# routev3_5_poly.net
KiCad netlist of a schematic drawn in EAGLE
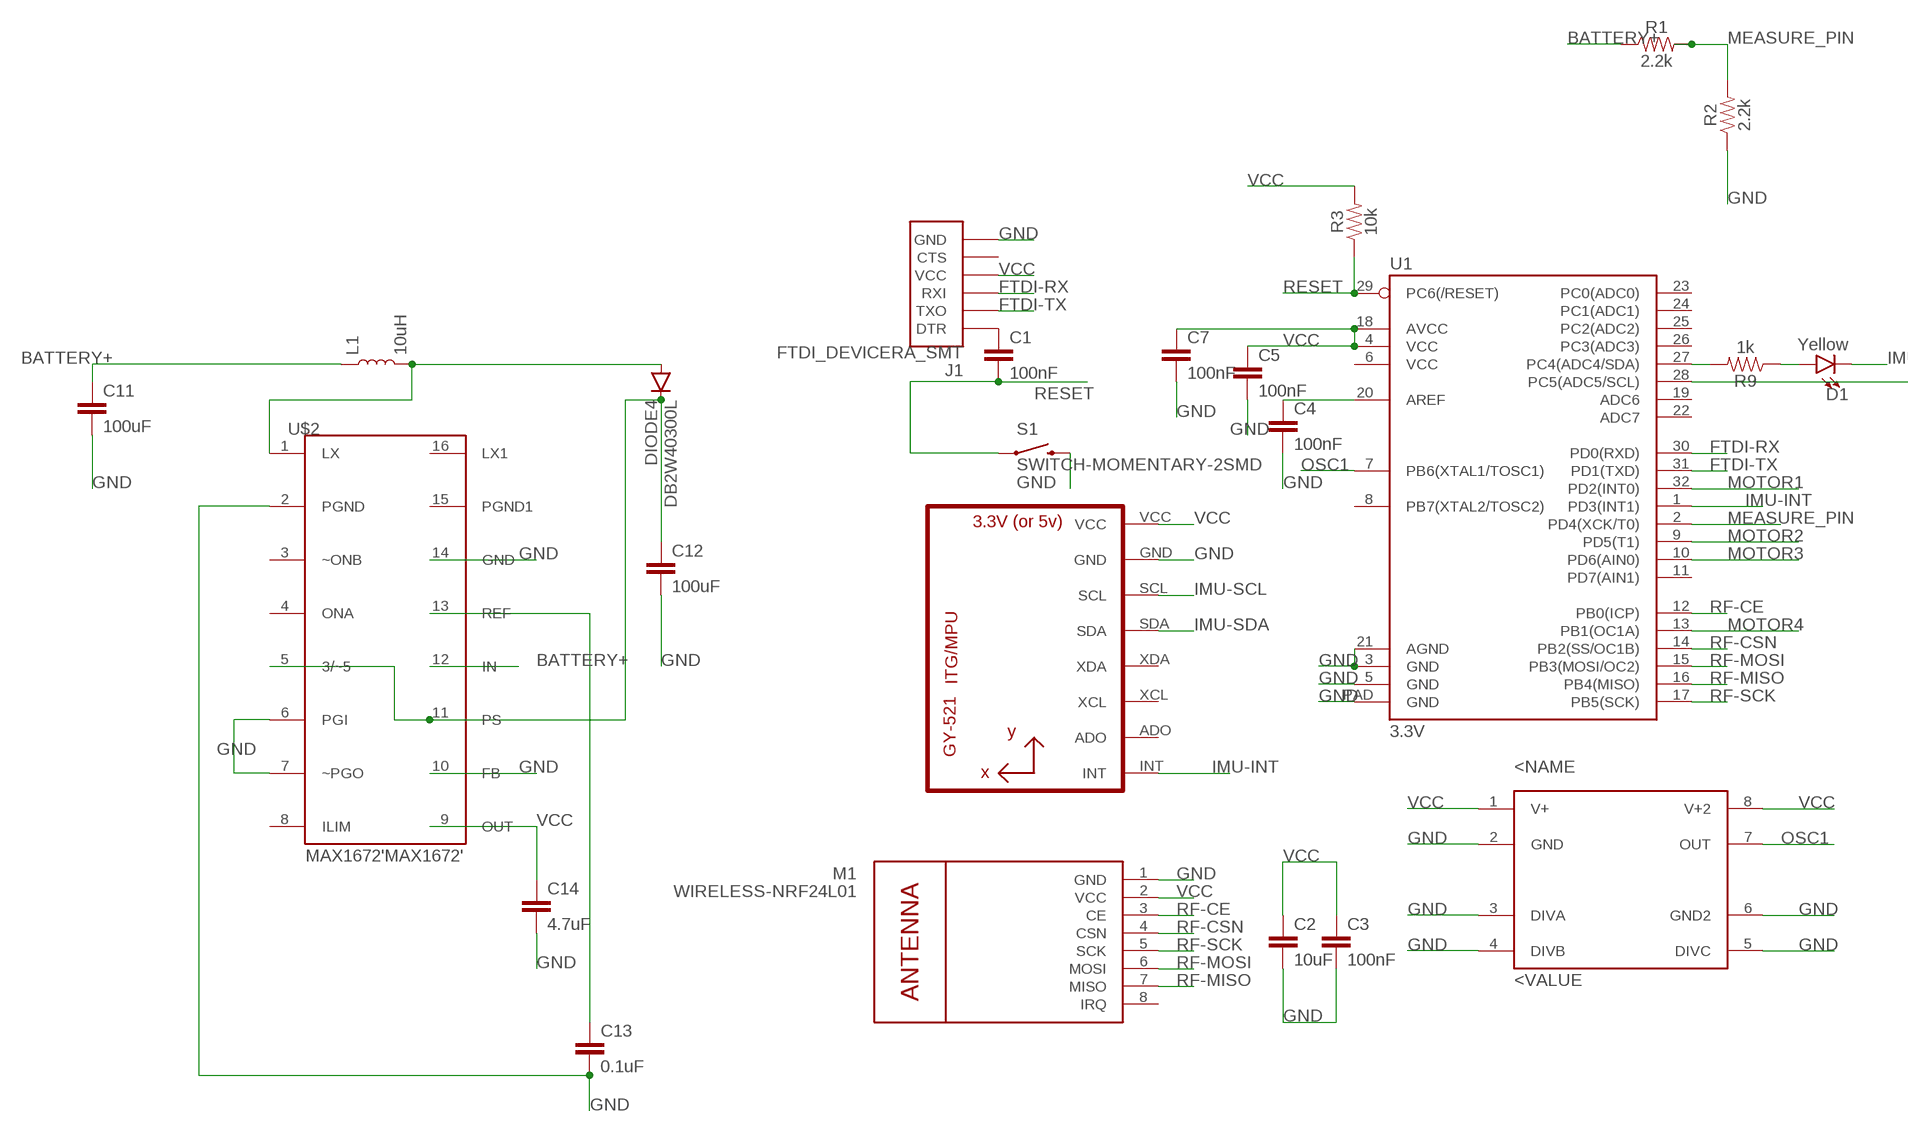
[diagram p0: schematic, sheet 1, part 1 of 2]
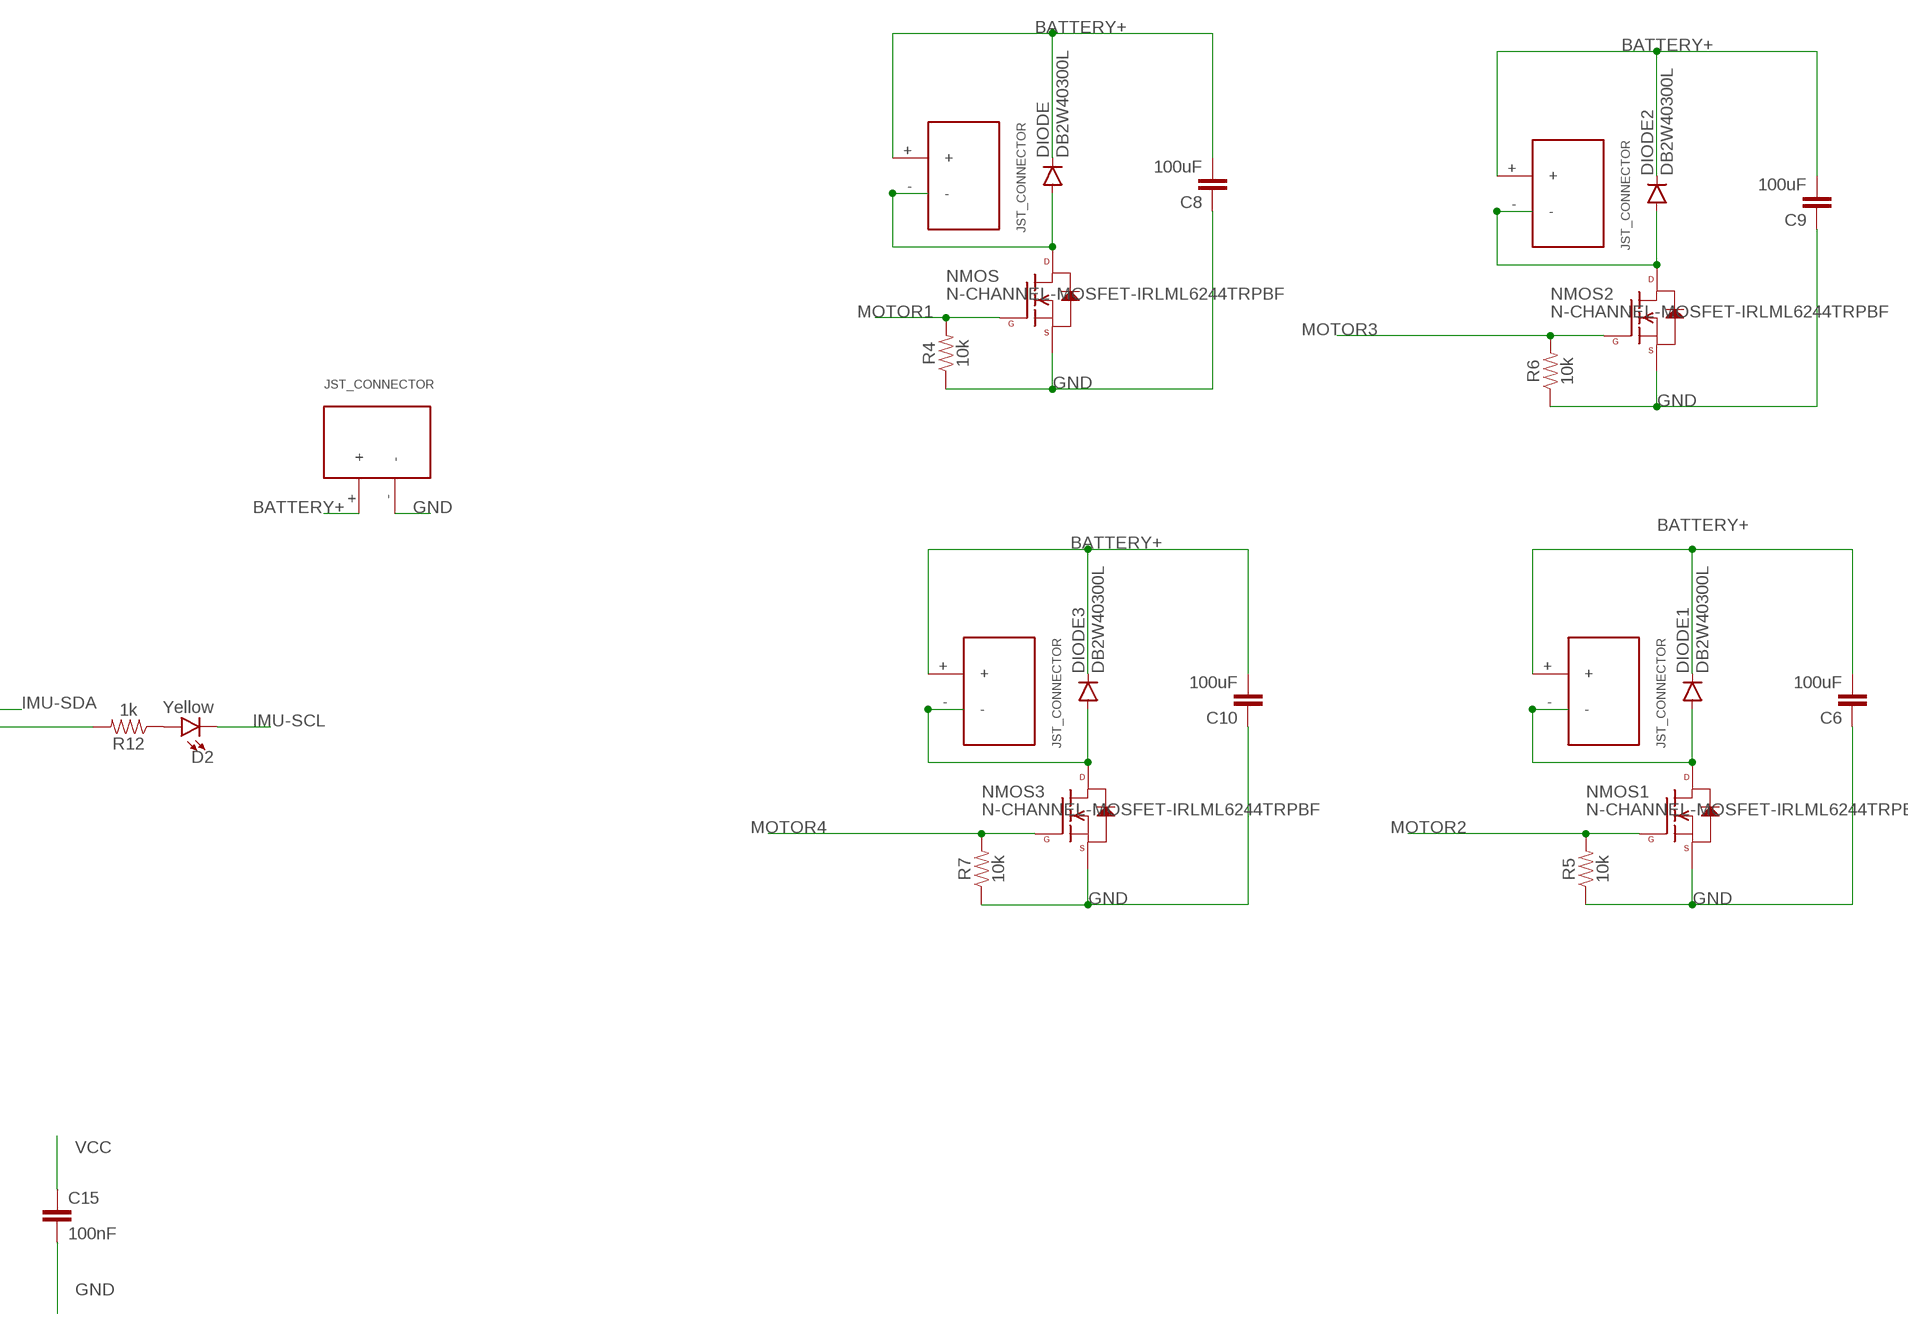
[diagram p1: schematic, sheet 1, part 2 of 2]

(export (version "E")
  (design (tool "Eeschema 10.0.6"))
  (components
    (comp (ref "C1")
      (value "100nF")
      (footprint "eagle-import:0603-CAP")
      (libsource (lib "eagle-import") (part "0.1UF-25V(+80/-20%)(0603)"))
    )
    (comp (ref "C2")
      (value "10uF")
      (footprint "eagle-import:0603-CAP")
      (libsource (lib "eagle-import") (part "CAP0603-CAP"))
    )
    (comp (ref "C3")
      (value "100nF")
      (footprint "eagle-import:0603-CAP")
      (libsource (lib "eagle-import") (part "CAP0603-CAP"))
    )
    (comp (ref "C4")
      (value "100nF")
      (footprint "eagle-import:0603-CAP")
      (libsource (lib "eagle-import") (part "CAP0603-CAP"))
    )
    (comp (ref "C5")
      (value "100nF")
      (footprint "eagle-import:0603-CAP")
      (libsource (lib "eagle-import") (part "CAP0603-CAP"))
    )
    (comp (ref "C6")
      (value "100uF")
      (footprint "eagle-import:0603-CAP")
      (libsource (lib "eagle-import") (part "CAP0603-CAP"))
    )
    (comp (ref "C7")
      (value "100nF")
      (footprint "eagle-import:0603-CAP")
      (libsource (lib "eagle-import") (part "CAP0603-CAP"))
    )
    (comp (ref "C8")
      (value "100uF")
      (footprint "eagle-import:0603-CAP")
      (libsource (lib "eagle-import") (part "CAP0603-CAP"))
    )
    (comp (ref "C9")
      (value "100uF")
      (footprint "eagle-import:0603-CAP")
      (libsource (lib "eagle-import") (part "CAP0603-CAP"))
    )
    (comp (ref "C10")
      (value "100uF")
      (footprint "eagle-import:0603-CAP")
      (libsource (lib "eagle-import") (part "CAP0603-CAP"))
    )
    (comp (ref "C11")
      (value "100uF")
      (footprint "eagle-import:0603-CAP")
      (libsource (lib "eagle-import") (part "CAP0603-CAP"))
    )
    (comp (ref "C12")
      (value "100uF")
      (footprint "eagle-import:0603-CAP")
      (libsource (lib "eagle-import") (part "CAP0603-CAP"))
    )
    (comp (ref "C13")
      (value "0.1uF")
      (footprint "eagle-import:0603-CAP")
      (libsource (lib "eagle-import") (part "CAP0603-CAP"))
    )
    (comp (ref "C14")
      (value "4.7uF")
      (footprint "eagle-import:0603-CAP")
      (libsource (lib "eagle-import") (part "CAP0603-CAP"))
    )
    (comp (ref "C15")
      (value "100nF")
      (footprint "eagle-import:0603-CAP")
      (libsource (lib "eagle-import") (part "0.1UF-25V(+80/-20%)(0603)"))
    )
    (comp (ref "D1")
      (value "Yellow")
      (footprint "eagle-import:LED-1206")
      (libsource (lib "eagle-import") (part "LED-YELLOWLILYPAD"))
    )
    (comp (ref "D2")
      (value "Yellow")
      (footprint "eagle-import:LED-1206")
      (libsource (lib "eagle-import") (part "LED-YELLOWLILYPAD"))
    )
    (comp (ref "DIODE")
      (value "DB2W40300L")
      (footprint "eagle-import:MINI2-F3-B")
      (libsource (lib "eagle-import") (part "DB2W40300L"))
    )
    (comp (ref "DIODE1")
      (value "DB2W40300L")
      (footprint "eagle-import:MINI2-F3-B")
      (libsource (lib "eagle-import") (part "DB2W40300L"))
    )
    (comp (ref "DIODE2")
      (value "DB2W40300L")
      (footprint "eagle-import:MINI2-F3-B")
      (libsource (lib "eagle-import") (part "DB2W40300L"))
    )
    (comp (ref "DIODE3")
      (value "DB2W40300L")
      (footprint "eagle-import:MINI2-F3-B")
      (libsource (lib "eagle-import") (part "DB2W40300L"))
    )
    (comp (ref "DIODE4")
      (value "DB2W40300L")
      (footprint "eagle-import:MINI2-F3-B")
      (libsource (lib "eagle-import") (part "DB2W40300L"))
    )
    (comp (ref "J1")
      (value "FTDI_DEVICERA_SMT")
      (footprint "eagle-import:FTDI_DEVICE_RA_SMT")
      (libsource (lib "eagle-import") (part "FTDI_DEVICERA_SMT"))
    )
    (comp (ref "L1")
      (value "10uH")
      (footprint "eagle-import:0603")
      (libsource (lib "eagle-import") (part "INDUCTOR-0603-33NH"))
    )
    (comp (ref "M1")
      (value "WIRELESS-NRF24L01")
      (footprint "eagle-import:WIRELESS-NRF24L01")
      (libsource (lib "eagle-import") (part "WIRELESS-NRF24L01"))
    )
    (comp (ref "MOTOR")
      (value "JST_CONNECTOR_FEMALE")
      (footprint "eagle-import:JST_CONNECTOR_FEMALE")
      (libsource (lib "eagle-import") (part "JST_CONNECTOR_FEMALE"))
    )
    (comp (ref "MOTOR1")
      (value "JST_CONNECTOR_FEMALE")
      (footprint "eagle-import:JST_CONNECTOR_FEMALE")
      (libsource (lib "eagle-import") (part "JST_CONNECTOR_FEMALE"))
    )
    (comp (ref "MOTOR2")
      (value "JST_CONNECTOR_FEMALE")
      (footprint "eagle-import:JST_CONNECTOR_FEMALE")
      (libsource (lib "eagle-import") (part "JST_CONNECTOR_FEMALE"))
    )
    (comp (ref "MOTOR3")
      (value "JST_CONNECTOR_FEMALE")
      (footprint "eagle-import:JST_CONNECTOR_FEMALE")
      (libsource (lib "eagle-import") (part "JST_CONNECTOR_FEMALE"))
    )
    (comp (ref "NMOS")
      (value "N-CHANNEL-MOSFET-IRLML6244TRPBF")
      (footprint "eagle-import:SOT23-3")
      (libsource (lib "eagle-import") (part "N-CHANNEL-MOSFET-IRLML6244TRPBF"))
    )
    (comp (ref "NMOS1")
      (value "N-CHANNEL-MOSFET-IRLML6244TRPBF")
      (footprint "eagle-import:SOT23-3")
      (libsource (lib "eagle-import") (part "N-CHANNEL-MOSFET-IRLML6244TRPBF"))
    )
    (comp (ref "NMOS2")
      (value "N-CHANNEL-MOSFET-IRLML6244TRPBF")
      (footprint "eagle-import:SOT23-3")
      (libsource (lib "eagle-import") (part "N-CHANNEL-MOSFET-IRLML6244TRPBF"))
    )
    (comp (ref "NMOS3")
      (value "N-CHANNEL-MOSFET-IRLML6244TRPBF")
      (footprint "eagle-import:SOT23-3")
      (libsource (lib "eagle-import") (part "N-CHANNEL-MOSFET-IRLML6244TRPBF"))
    )
    (comp (ref "R1")
      (value "2.2k")
      (footprint "eagle-import:0603")
      (libsource (lib "eagle-import") (part "2.2KOHM-0603-1/10W-1%"))
    )
    (comp (ref "R2")
      (value "2.2k")
      (footprint "eagle-import:0603")
      (libsource (lib "eagle-import") (part "2.2KOHM-0603-1/10W-1%"))
    )
    (comp (ref "R3")
      (value "10k")
      (footprint "eagle-import:0603")
      (libsource (lib "eagle-import") (part "2.2KOHM-0603-1/10W-1%"))
    )
    (comp (ref "R4")
      (value "10k")
      (footprint "eagle-import:0603")
      (libsource (lib "eagle-import") (part "2.2KOHM-0603-1/10W-1%"))
    )
    (comp (ref "R5")
      (value "10k")
      (footprint "eagle-import:0603")
      (libsource (lib "eagle-import") (part "2.2KOHM-0603-1/10W-1%"))
    )
    (comp (ref "R6")
      (value "10k")
      (footprint "eagle-import:0603")
      (libsource (lib "eagle-import") (part "2.2KOHM-0603-1/10W-1%"))
    )
    (comp (ref "R7")
      (value "10k")
      (footprint "eagle-import:0603")
      (libsource (lib "eagle-import") (part "2.2KOHM-0603-1/10W-1%"))
    )
    (comp (ref "R9")
      (value "1k")
      (footprint "eagle-import:0603")
      (libsource (lib "eagle-import") (part "2.2KOHM-0603-1/10W-1%"))
    )
    (comp (ref "R12")
      (value "1k")
      (footprint "eagle-import:0603")
      (libsource (lib "eagle-import") (part "2.2KOHM-0603-1/10W-1%"))
    )
    (comp (ref "S1")
      (value "SWITCH-MOMENTARY-2SMD")
      (footprint "eagle-import:TACTILE-SWITCH-SMD")
      (libsource (lib "eagle-import") (part "SWITCH-MOMENTARY-2SMD"))
    )
    (comp (ref "U$1")
      (value "JST_CONNECTOR_FEMALE")
      (footprint "eagle-import:JST_CONNECTOR_FEMALE")
      (libsource (lib "eagle-import") (part "JST_CONNECTOR_FEMALE"))
    )
    (comp (ref "U$2")
      (value "MAX1672'MAX1672'")
      (footprint "eagle-import:21-0055H_16")
      (libsource (lib "eagle-import") (part "MAX1672'MAX1672'"))
    )
    (comp (ref "U$3")
      (value "LTC6930CMS8-8.19LTC6930CMS8-8.19")
      (footprint "eagle-import:SOP65P490X110-8N")
      (libsource (lib "eagle-import") (part "LTC6930CMS8-8.19LTC6930CMS8-8.19"))
    )
    (comp (ref "U1")
      (value "3.3V")
      (footprint "eagle-import:MLF32-PAD")
      (libsource (lib "eagle-import") (part "ATMEGA328P_MLFMLF32"))
    )
    (comp (ref "U2")
      (value "GY-521MPU6050")
      (footprint "eagle-import:GY-521")
      (libsource (lib "eagle-import") (part "GY-521MPU6050"))
    )
  )
  (nets
    (net (code "1") (name "BATTERY+") (class "Default")
      (node (ref "C10") (pin "2") (pinfunction "2_2") (pintype "passive"))
      (node (ref "C11") (pin "1") (pinfunction "1_1") (pintype "passive"))
      (node (ref "C6") (pin "2") (pinfunction "2_2") (pintype "passive"))
      (node (ref "C8") (pin "2") (pinfunction "2_2") (pintype "passive"))
      (node (ref "C9") (pin "2") (pinfunction "2_2") (pintype "passive"))
      (node (ref "DIODE") (pin "NEG") (pinfunction "GPIN_NEG") (pintype "passive"))
      (node (ref "DIODE1") (pin "NEG") (pinfunction "GPIN_NEG") (pintype "passive"))
      (node (ref "DIODE2") (pin "NEG") (pinfunction "GPIN_NEG") (pintype "passive"))
      (node (ref "DIODE3") (pin "NEG") (pinfunction "GPIN_NEG") (pintype "passive"))
      (node (ref "L1") (pin "1") (pinfunction "1_1") (pintype "passive"))
      (node (ref "MOTOR") (pin "+") (pinfunction "+_+") (pintype "bidirectional"))
      (node (ref "MOTOR1") (pin "+") (pinfunction "+_+") (pintype "bidirectional"))
      (node (ref "MOTOR2") (pin "+") (pinfunction "+_+") (pintype "bidirectional"))
      (node (ref "MOTOR3") (pin "+") (pinfunction "+_+") (pintype "bidirectional"))
      (node (ref "R1") (pin "1") (pinfunction "1_1") (pintype "passive"))
      (node (ref "U$1") (pin "+") (pinfunction "+_+") (pintype "bidirectional"))
      (node (ref "U$2") (pin "12") (pinfunction "IN_12") (pintype "bidirectional"))
    )
    (net (code "2") (name "FTDI-RX") (class "Default")
      (node (ref "J1") (pin "3") (pinfunction "RXI_3") (pintype "bidirectional"))
      (node (ref "U1") (pin "30") (pinfunction "PD0(RXD)_30") (pintype "bidirectional"))
    )
    (net (code "3") (name "FTDI-TX") (class "Default")
      (node (ref "J1") (pin "2") (pinfunction "TXO_2") (pintype "bidirectional"))
      (node (ref "U1") (pin "31") (pinfunction "PD1(TXD)_31") (pintype "bidirectional"))
    )
    (net (code "4") (name "GND") (class "Default")
      (node (ref "C10") (pin "1") (pinfunction "1_1") (pintype "passive"))
      (node (ref "C11") (pin "2") (pinfunction "2_2") (pintype "passive"))
      (node (ref "C12") (pin "2") (pinfunction "2_2") (pintype "passive"))
      (node (ref "C13") (pin "2") (pinfunction "2_2") (pintype "passive"))
      (node (ref "C14") (pin "2") (pinfunction "2_2") (pintype "passive"))
      (node (ref "C15") (pin "2") (pinfunction "2_2") (pintype "passive"))
      (node (ref "C2") (pin "2") (pinfunction "2_2") (pintype "passive"))
      (node (ref "C3") (pin "2") (pinfunction "2_2") (pintype "passive"))
      (node (ref "C4") (pin "2") (pinfunction "2_2") (pintype "passive"))
      (node (ref "C5") (pin "2") (pinfunction "2_2") (pintype "passive"))
      (node (ref "C6") (pin "1") (pinfunction "1_1") (pintype "passive"))
      (node (ref "C7") (pin "2") (pinfunction "2_2") (pintype "passive"))
      (node (ref "C8") (pin "1") (pinfunction "1_1") (pintype "passive"))
      (node (ref "C9") (pin "1") (pinfunction "1_1") (pintype "passive"))
      (node (ref "J1") (pin "6") (pinfunction "GND_6") (pintype "bidirectional"))
      (node (ref "M1") (pin "1") (pinfunction "GND_1") (pintype "power_in"))
      (node (ref "NMOS") (pin "2") (pinfunction "S_2") (pintype "passive"))
      (node (ref "NMOS1") (pin "2") (pinfunction "S_2") (pintype "passive"))
      (node (ref "NMOS2") (pin "2") (pinfunction "S_2") (pintype "passive"))
      (node (ref "NMOS3") (pin "2") (pinfunction "S_2") (pintype "passive"))
      (node (ref "R2") (pin "1") (pinfunction "1_1") (pintype "passive"))
      (node (ref "R4") (pin "1") (pinfunction "1_1") (pintype "passive"))
      (node (ref "R5") (pin "1") (pinfunction "1_1") (pintype "passive"))
      (node (ref "R6") (pin "1") (pinfunction "1_1") (pintype "passive"))
      (node (ref "R7") (pin "1") (pinfunction "1_1") (pintype "passive"))
      (node (ref "S1") (pin "3") (pinfunction "2_3") (pintype "passive"))
      (node (ref "U$1") (pin "-") (pinfunction "-_-") (pintype "bidirectional"))
      (node (ref "U$2") (pin "10") (pinfunction "FB_10") (pintype "bidirectional"))
      (node (ref "U$2") (pin "14") (pinfunction "GND_14") (pintype "bidirectional"))
      (node (ref "U$2") (pin "2") (pinfunction "PGND_2") (pintype "bidirectional"))
      (node (ref "U$2") (pin "6") (pinfunction "PGI_6") (pintype "bidirectional"))
      (node (ref "U$2") (pin "7") (pinfunction "~{PGO}_7") (pintype "bidirectional"))
      (node (ref "U$3") (pin "2") (pinfunction "GND_2") (pintype "bidirectional"))
      (node (ref "U$3") (pin "3") (pinfunction "DIVA_3") (pintype "bidirectional"))
      (node (ref "U$3") (pin "4") (pinfunction "DIVB_4") (pintype "bidirectional"))
      (node (ref "U$3") (pin "5") (pinfunction "DIVC_5") (pintype "bidirectional"))
      (node (ref "U$3") (pin "6") (pinfunction "GND2_6") (pintype "bidirectional"))
      (node (ref "U1") (pin "21") (pinfunction "AGND_21") (pintype "bidirectional"))
      (node (ref "U1") (pin "3") (pinfunction "GND_3") (pintype "bidirectional"))
      (node (ref "U1") (pin "5") (pinfunction "GND_5") (pintype "bidirectional"))
      (node (ref "U1") (pin "PAD") (pinfunction "GND_PAD") (pintype "bidirectional"))
      (node (ref "U2") (pin "GND") (pinfunction "GND_GND") (pintype "bidirectional"))
    )
    (net (code "5") (name "IMU-INT") (class "Default")
      (node (ref "U1") (pin "1") (pinfunction "PD3(INT1)_1") (pintype "bidirectional"))
      (node (ref "U2") (pin "INT") (pinfunction "INT_INT") (pintype "bidirectional"))
    )
    (net (code "6") (name "IMU-SCL") (class "Default")
      (node (ref "D2") (pin "C") (pinfunction "C_C") (pintype "passive"))
      (node (ref "U2") (pin "SCL") (pinfunction "SCL_SCL") (pintype "bidirectional"))
    )
    (net (code "7") (name "IMU-SDA") (class "Default")
      (node (ref "D1") (pin "C") (pinfunction "C_C") (pintype "passive"))
      (node (ref "U2") (pin "SDA") (pinfunction "SDA_SDA") (pintype "bidirectional"))
    )
    (net (code "8") (name "MEASURE_PIN") (class "Default")
      (node (ref "R1") (pin "2") (pinfunction "2_2") (pintype "passive"))
      (node (ref "R2") (pin "2") (pinfunction "2_2") (pintype "passive"))
      (node (ref "U1") (pin "2") (pinfunction "PD4(XCK/T0)_2") (pintype "bidirectional"))
    )
    (net (code "9") (name "MOTOR1") (class "Default")
      (node (ref "NMOS") (pin "1") (pinfunction "G_1") (pintype "passive"))
      (node (ref "R4") (pin "2") (pinfunction "2_2") (pintype "passive"))
      (node (ref "U1") (pin "32") (pinfunction "PD2(INT0)_32") (pintype "bidirectional"))
    )
    (net (code "10") (name "MOTOR2") (class "Default")
      (node (ref "NMOS1") (pin "1") (pinfunction "G_1") (pintype "passive"))
      (node (ref "R5") (pin "2") (pinfunction "2_2") (pintype "passive"))
      (node (ref "U1") (pin "9") (pinfunction "PD5(T1)_9") (pintype "bidirectional"))
    )
    (net (code "11") (name "MOTOR3") (class "Default")
      (node (ref "NMOS2") (pin "1") (pinfunction "G_1") (pintype "passive"))
      (node (ref "R6") (pin "2") (pinfunction "2_2") (pintype "passive"))
      (node (ref "U1") (pin "10") (pinfunction "PD6(AIN0)_10") (pintype "bidirectional"))
    )
    (net (code "12") (name "MOTOR4") (class "Default")
      (node (ref "NMOS3") (pin "1") (pinfunction "G_1") (pintype "passive"))
      (node (ref "R7") (pin "2") (pinfunction "2_2") (pintype "passive"))
      (node (ref "U1") (pin "13") (pinfunction "PB1(OC1A)_13") (pintype "bidirectional"))
    )
    (net (code "13") (name "Net-(D1-PadA)") (class "Default")
      (node (ref "D1") (pin "A") (pinfunction "A_A") (pintype "passive"))
      (node (ref "R9") (pin "1") (pinfunction "1_1") (pintype "passive"))
    )
    (net (code "14") (name "Net-(D2-PadA)") (class "Default")
      (node (ref "D2") (pin "A") (pinfunction "A_A") (pintype "passive"))
      (node (ref "R12") (pin "1") (pinfunction "1_1") (pintype "passive"))
    )
    (net (code "15") (name "Net-(DIODE-PPIN)") (class "Default")
      (node (ref "DIODE") (pin "POS") (pinfunction "PPIN_POS") (pintype "passive"))
      (node (ref "MOTOR") (pin "-") (pinfunction "-_-") (pintype "bidirectional"))
      (node (ref "NMOS") (pin "3") (pinfunction "D_3") (pintype "passive"))
    )
    (net (code "16") (name "Net-(DIODE1-PPIN)") (class "Default")
      (node (ref "DIODE1") (pin "POS") (pinfunction "PPIN_POS") (pintype "passive"))
      (node (ref "MOTOR1") (pin "-") (pinfunction "-_-") (pintype "bidirectional"))
      (node (ref "NMOS1") (pin "3") (pinfunction "D_3") (pintype "passive"))
    )
    (net (code "17") (name "Net-(DIODE2-PPIN)") (class "Default")
      (node (ref "DIODE2") (pin "POS") (pinfunction "PPIN_POS") (pintype "passive"))
      (node (ref "MOTOR2") (pin "-") (pinfunction "-_-") (pintype "bidirectional"))
      (node (ref "NMOS2") (pin "3") (pinfunction "D_3") (pintype "passive"))
    )
    (net (code "18") (name "Net-(DIODE3-PPIN)") (class "Default")
      (node (ref "DIODE3") (pin "POS") (pinfunction "PPIN_POS") (pintype "passive"))
      (node (ref "MOTOR3") (pin "-") (pinfunction "-_-") (pintype "bidirectional"))
      (node (ref "NMOS3") (pin "3") (pinfunction "D_3") (pintype "passive"))
    )
    (net (code "19") (name "Net-(DIODE4-GPIN)") (class "Default")
      (node (ref "C12") (pin "1") (pinfunction "1_1") (pintype "passive"))
      (node (ref "DIODE4") (pin "NEG") (pinfunction "GPIN_NEG") (pintype "passive"))
      (node (ref "U$2") (pin "11") (pinfunction "PS_11") (pintype "bidirectional"))
      (node (ref "U$2") (pin "5") (pinfunction "3/~{5}_5") (pintype "bidirectional"))
    )
    (net (code "20") (name "Net-(DIODE4-PPIN)") (class "Default")
      (node (ref "DIODE4") (pin "POS") (pinfunction "PPIN_POS") (pintype "passive"))
      (node (ref "L1") (pin "2") (pinfunction "2_2") (pintype "passive"))
      (node (ref "U$2") (pin "1") (pinfunction "LX_1") (pintype "bidirectional"))
    )
    (net (code "21") (name "Net-(J1-DTR)") (class "Default")
      (node (ref "C1") (pin "1") (pinfunction "1_1") (pintype "passive"))
      (node (ref "J1") (pin "1") (pinfunction "DTR_1") (pintype "bidirectional"))
    )
    (net (code "22") (name "Net-(U$2-REF)") (class "Default")
      (node (ref "C13") (pin "1") (pinfunction "1_1") (pintype "passive"))
      (node (ref "U$2") (pin "13") (pinfunction "REF_13") (pintype "bidirectional"))
    )
    (net (code "23") (name "Net-(U1-AREF)") (class "Default")
      (node (ref "C4") (pin "1") (pinfunction "1_1") (pintype "passive"))
      (node (ref "U1") (pin "20") (pinfunction "AREF_20") (pintype "bidirectional"))
    )
    (net (code "24") (name "Net-(U1-PC4(ADC4{slash}SDA))") (class "Default")
      (node (ref "R9") (pin "2") (pinfunction "2_2") (pintype "passive"))
      (node (ref "U1") (pin "27") (pinfunction "PC4(ADC4/SDA)_27") (pintype "bidirectional"))
    )
    (net (code "25") (name "Net-(U1-PC5(ADC5{slash}SCL))") (class "Default")
      (node (ref "R12") (pin "2") (pinfunction "2_2") (pintype "passive"))
      (node (ref "U1") (pin "28") (pinfunction "PC5(ADC5/SCL)_28") (pintype "bidirectional"))
    )
    (net (code "26") (name "OSC1") (class "Default")
      (node (ref "U$3") (pin "7") (pinfunction "OUT_7") (pintype "bidirectional"))
      (node (ref "U1") (pin "7") (pinfunction "PB6(XTAL1/TOSC1)_7") (pintype "bidirectional"))
    )
    (net (code "27") (name "RESET") (class "Default")
      (node (ref "C1") (pin "2") (pinfunction "2_2") (pintype "passive"))
      (node (ref "R3") (pin "1") (pinfunction "1_1") (pintype "passive"))
      (node (ref "S1") (pin "1") (pinfunction "1_1") (pintype "passive"))
      (node (ref "U1") (pin "29") (pinfunction "PC6(/RESET)_29") (pintype "bidirectional"))
    )
    (net (code "28") (name "RF-CE") (class "Default")
      (node (ref "M1") (pin "3") (pinfunction "CE_3") (pintype "bidirectional"))
      (node (ref "U1") (pin "12") (pinfunction "PB0(ICP)_12") (pintype "bidirectional"))
    )
    (net (code "29") (name "RF-CSN") (class "Default")
      (node (ref "M1") (pin "4") (pinfunction "CSN_4") (pintype "bidirectional"))
      (node (ref "U1") (pin "14") (pinfunction "PB2(SS/OC1B)_14") (pintype "bidirectional"))
    )
    (net (code "30") (name "RF-MISO") (class "Default")
      (node (ref "M1") (pin "7") (pinfunction "MISO_7") (pintype "bidirectional"))
      (node (ref "U1") (pin "16") (pinfunction "PB4(MISO)_16") (pintype "bidirectional"))
    )
    (net (code "31") (name "RF-MOSI") (class "Default")
      (node (ref "M1") (pin "6") (pinfunction "MOSI_6") (pintype "bidirectional"))
      (node (ref "U1") (pin "15") (pinfunction "PB3(MOSI/OC2)_15") (pintype "bidirectional"))
    )
    (net (code "32") (name "RF-SCK") (class "Default")
      (node (ref "M1") (pin "5") (pinfunction "SCK_5") (pintype "bidirectional"))
      (node (ref "U1") (pin "17") (pinfunction "PB5(SCK)_17") (pintype "bidirectional"))
    )
    (net (code "33") (name "VCC") (class "Default")
      (node (ref "C14") (pin "1") (pinfunction "1_1") (pintype "passive"))
      (node (ref "C15") (pin "1") (pinfunction "1_1") (pintype "passive"))
      (node (ref "C2") (pin "1") (pinfunction "1_1") (pintype "passive"))
      (node (ref "C3") (pin "1") (pinfunction "1_1") (pintype "passive"))
      (node (ref "C5") (pin "1") (pinfunction "1_1") (pintype "passive"))
      (node (ref "C7") (pin "1") (pinfunction "1_1") (pintype "passive"))
      (node (ref "J1") (pin "4") (pinfunction "VCC_4") (pintype "bidirectional"))
      (node (ref "M1") (pin "2") (pinfunction "VCC_2") (pintype "power_in"))
      (node (ref "R3") (pin "2") (pinfunction "2_2") (pintype "passive"))
      (node (ref "U$2") (pin "9") (pinfunction "OUT_9") (pintype "bidirectional"))
      (node (ref "U$3") (pin "1") (pinfunction "V+_1") (pintype "bidirectional"))
      (node (ref "U$3") (pin "8") (pinfunction "V+2_8") (pintype "bidirectional"))
      (node (ref "U1") (pin "18") (pinfunction "AVCC_18") (pintype "bidirectional"))
      (node (ref "U1") (pin "4") (pinfunction "VCC_4") (pintype "bidirectional"))
      (node (ref "U2") (pin "VCC") (pinfunction "VCC_VCC") (pintype "bidirectional"))
    )
    (net (code "34") (name "unconnected-(J1-CTS-Pad5)") (class "Default")
      (node (ref "J1") (pin "5") (pinfunction "CTS_5") (pintype "bidirectional"))
    )
    (net (code "35") (name "unconnected-(M1-IRQ-Pad8)") (class "Default")
      (node (ref "M1") (pin "8") (pinfunction "IRQ_8") (pintype "bidirectional"))
    )
    (net (code "36") (name "unconnected-(U$2-ILIM-Pad8)") (class "Default")
      (node (ref "U$2") (pin "8") (pinfunction "ILIM_8") (pintype "bidirectional"))
    )
    (net (code "37") (name "unconnected-(U$2-LX1-Pad16)") (class "Default")
      (node (ref "U$2") (pin "16") (pinfunction "LX1_16") (pintype "bidirectional"))
    )
    (net (code "38") (name "unconnected-(U$2-ONA-Pad4)") (class "Default")
      (node (ref "U$2") (pin "4") (pinfunction "ONA_4") (pintype "bidirectional"))
    )
    (net (code "39") (name "unconnected-(U$2-PGND1-Pad15)") (class "Default")
      (node (ref "U$2") (pin "15") (pinfunction "PGND1_15") (pintype "bidirectional"))
    )
    (net (code "40") (name "unconnected-(U$2-~{ONB}-Pad3)") (class "Default")
      (node (ref "U$2") (pin "3") (pinfunction "~{ONB}_3") (pintype "bidirectional"))
    )
    (net (code "41") (name "unconnected-(U1-ADC6-Pad19)") (class "Default")
      (node (ref "U1") (pin "19") (pinfunction "ADC6_19") (pintype "bidirectional"))
    )
    (net (code "42") (name "unconnected-(U1-ADC7-Pad22)") (class "Default")
      (node (ref "U1") (pin "22") (pinfunction "ADC7_22") (pintype "bidirectional"))
    )
    (net (code "43") (name "unconnected-(U1-PB7(XTAL2{slash}TOSC2)-Pad8)") (class "Default")
      (node (ref "U1") (pin "8") (pinfunction "PB7(XTAL2/TOSC2)_8") (pintype "bidirectional"))
    )
    (net (code "44") (name "unconnected-(U1-PC0(ADC0)-Pad23)") (class "Default")
      (node (ref "U1") (pin "23") (pinfunction "PC0(ADC0)_23") (pintype "bidirectional"))
    )
    (net (code "45") (name "unconnected-(U1-PC1(ADC1)-Pad24)") (class "Default")
      (node (ref "U1") (pin "24") (pinfunction "PC1(ADC1)_24") (pintype "bidirectional"))
    )
    (net (code "46") (name "unconnected-(U1-PC2(ADC2)-Pad25)") (class "Default")
      (node (ref "U1") (pin "25") (pinfunction "PC2(ADC2)_25") (pintype "bidirectional"))
    )
    (net (code "47") (name "unconnected-(U1-PC3(ADC3)-Pad26)") (class "Default")
      (node (ref "U1") (pin "26") (pinfunction "PC3(ADC3)_26") (pintype "bidirectional"))
    )
    (net (code "48") (name "unconnected-(U1-PD7(AIN1)-Pad11)") (class "Default")
      (node (ref "U1") (pin "11") (pinfunction "PD7(AIN1)_11") (pintype "bidirectional"))
    )
    (net (code "49") (name "unconnected-(U1-VCC-Pad6)") (class "Default")
      (node (ref "U1") (pin "6") (pinfunction "VCC_6") (pintype "bidirectional"))
    )
    (net (code "50") (name "unconnected-(U2-PadADO)") (class "Default")
      (node (ref "U2") (pin "ADO") (pinfunction "ADO_ADO") (pintype "bidirectional"))
    )
    (net (code "51") (name "unconnected-(U2-PadXCL)") (class "Default")
      (node (ref "U2") (pin "XCL") (pinfunction "XCL_XCL") (pintype "bidirectional"))
    )
    (net (code "52") (name "unconnected-(U2-PadXDA)") (class "Default")
      (node (ref "U2") (pin "XDA") (pinfunction "XDA_XDA") (pintype "bidirectional"))
    )
  )
)
